# mapleCUx_large_102.net
KiCad netlist of a schematic drawn in EAGLE
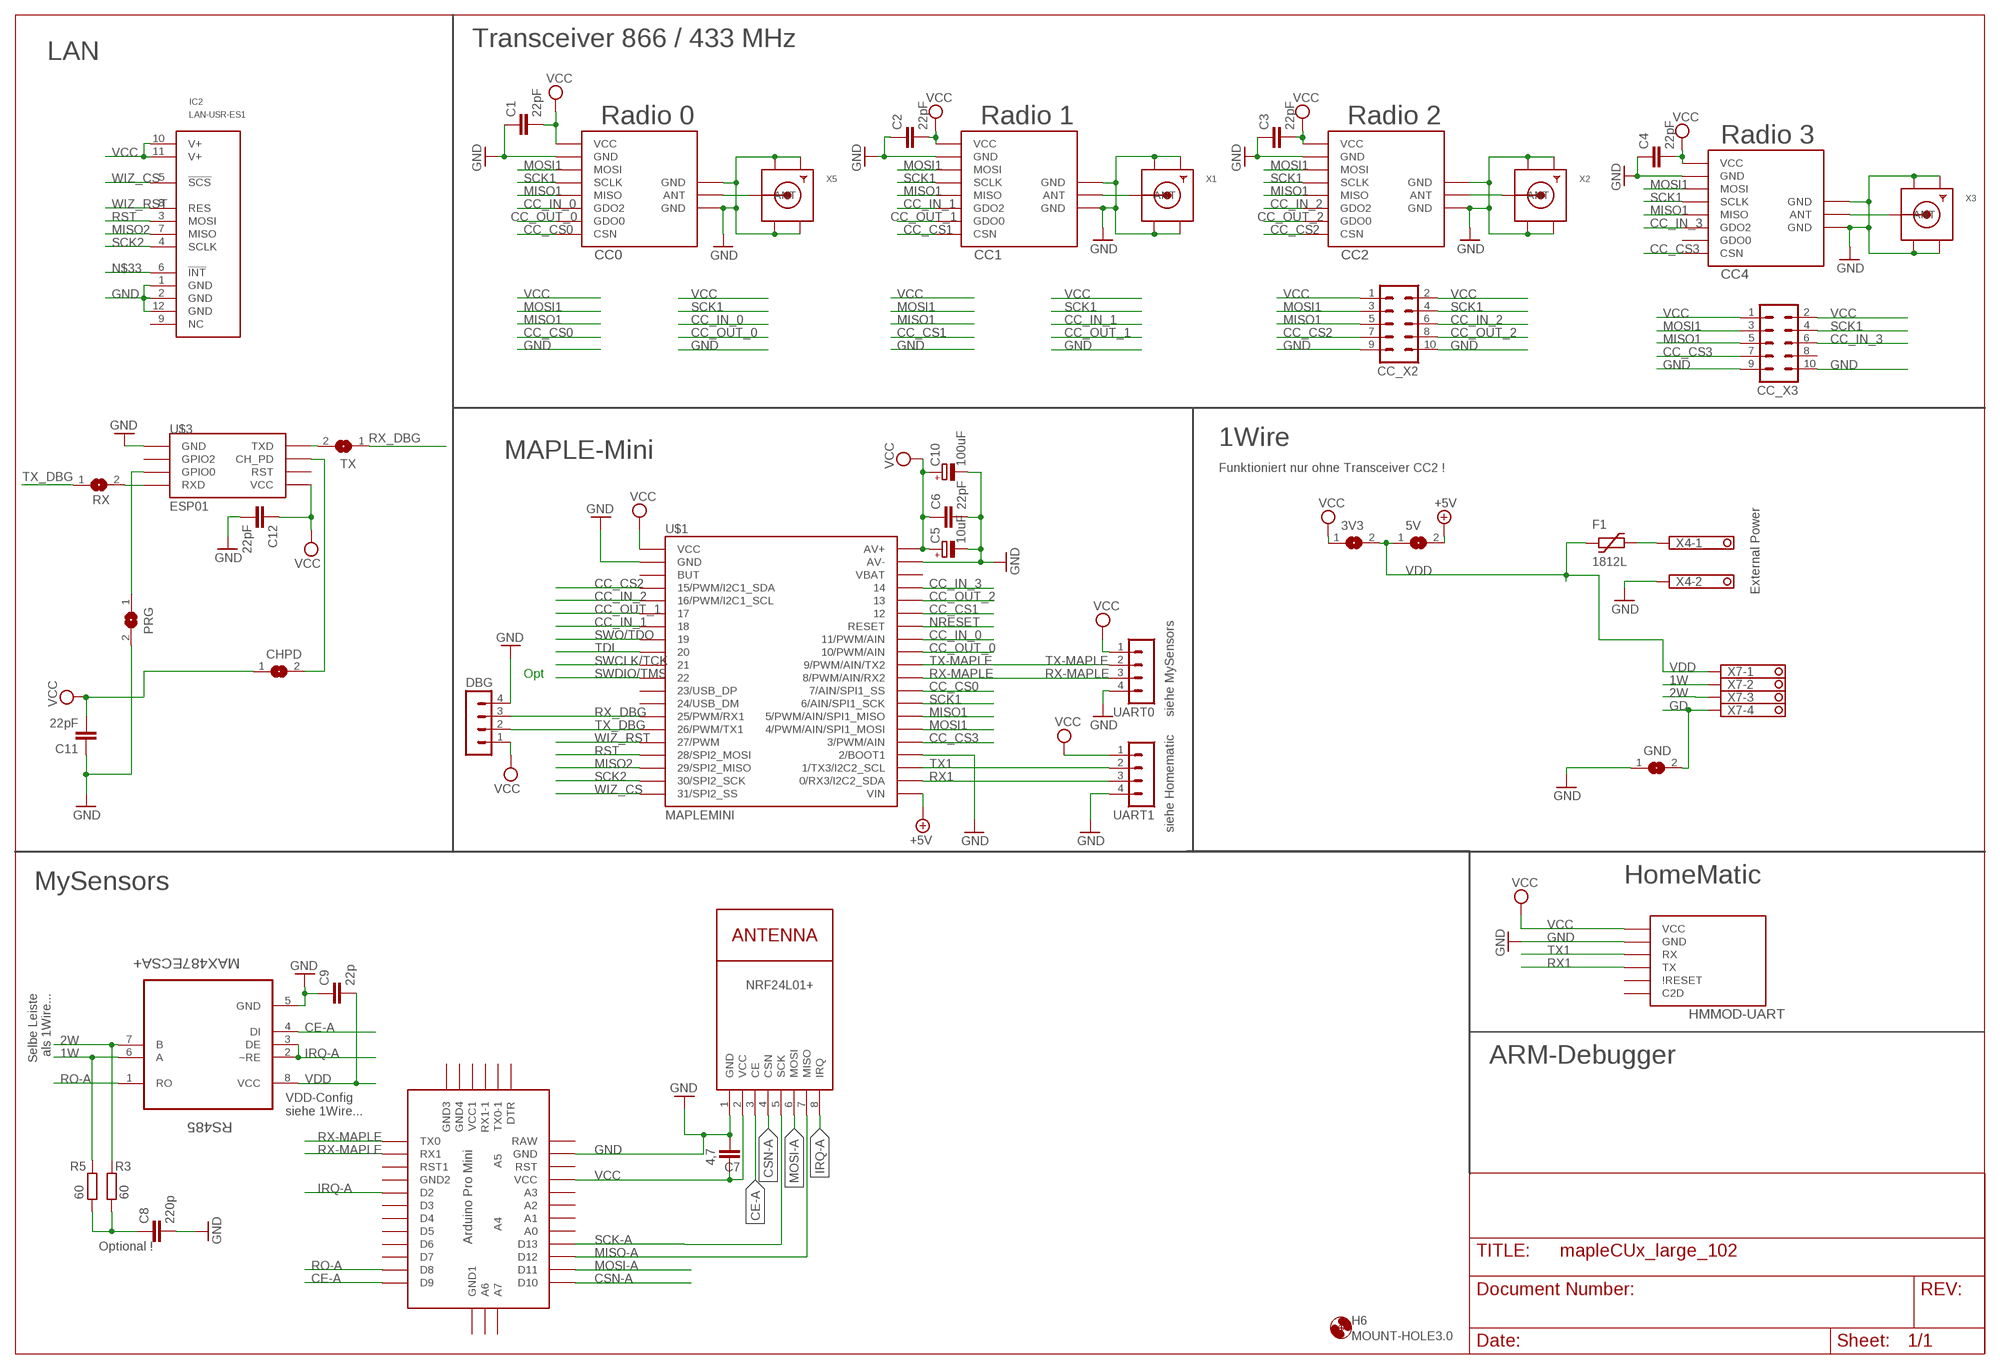
[diagram p0: schematic, sheet 1]

(export (version "E")
  (design (tool "Eeschema 10.0.6"))
  (components
    (comp (ref "3V3") (value "SJ") (footprint "eagle-import:SJ") (libsource (lib "eagle-import") (part "SJ")))
    (comp (ref "5V") (value "SJ") (footprint "eagle-import:SJ") (libsource (lib "eagle-import") (part "SJ")))
    (comp (ref "C1")
      (value "22pF")
      (footprint "eagle-import:C0805")
      (libsource (lib "eagle-import") (part "C-EUC0805"))
    )
    (comp (ref "C2")
      (value "22pF")
      (footprint "eagle-import:C0805")
      (libsource (lib "eagle-import") (part "C-EUC0805"))
    )
    (comp (ref "C3")
      (value "22pF")
      (footprint "eagle-import:C0805")
      (libsource (lib "eagle-import") (part "C-EUC0805"))
    )
    (comp (ref "C4")
      (value "22pF")
      (footprint "eagle-import:C0805")
      (libsource (lib "eagle-import") (part "C-EUC0805"))
    )
    (comp (ref "C5")
      (value "10uF")
      (footprint "eagle-import:R_2012-12W")
      (libsource (lib "eagle-import") (part "CPOL-EUR/2012-12W"))
    )
    (comp (ref "C6")
      (value "22pF")
      (footprint "eagle-import:C0805")
      (libsource (lib "eagle-import") (part "C-EUC0805"))
    )
    (comp (ref "C7")
      (value "4,7")
      (footprint "eagle-import:C1210")
      (libsource (lib "eagle-import") (part "C-EUC1210"))
    )
    (comp (ref "C8")
      (value "220p")
      (footprint "eagle-import:C0805")
      (libsource (lib "eagle-import") (part "C-EUC0805"))
    )
    (comp (ref "C9")
      (value "22p")
      (footprint "eagle-import:C0805")
      (libsource (lib "eagle-import") (part "C-EUC0805"))
    )
    (comp (ref "C10")
      (value "100uF")
      (footprint "eagle-import:E5-8,5")
      (libsource (lib "eagle-import") (part "CPOL-EUE5-8.5"))
    )
    (comp (ref "C11")
      (value "22pF")
      (footprint "eagle-import:C0805")
      (libsource (lib "eagle-import") (part "C-EUC0805"))
    )
    (comp (ref "C12")
      (value "22pF")
      (footprint "eagle-import:C0805")
      (libsource (lib "eagle-import") (part "C-EUC0805"))
    )
    (comp (ref "CC0")
      (value "CC1101")
      (footprint "eagle-import:CC1101_MODULE1_SMD")
      (libsource (lib "eagle-import") (part "CC1101_MODULE1SMD"))
    )
    (comp (ref "CC1")
      (value "CC1101_MODULE1SMD")
      (footprint "eagle-import:CC1101_MODULE1_SMD")
      (libsource (lib "eagle-import") (part "CC1101_MODULE1SMD"))
    )
    (comp (ref "CC2")
      (value "CC1101_MODULE1SMD")
      (footprint "eagle-import:CC1101_MODULE1_SMD")
      (libsource (lib "eagle-import") (part "CC1101_MODULE1SMD"))
    )
    (comp (ref "CC4")
      (value "CC1101_MODULE1SMD")
      (footprint "eagle-import:CC1101_MODULE1_SMD")
      (libsource (lib "eagle-import") (part "CC1101_MODULE1SMD"))
    )
    (comp (ref "CC_X2")
      (value "MA05-2")
      (footprint "eagle-import:MA05-2")
      (libsource (lib "eagle-import") (part "MA05-2"))
    )
    (comp (ref "CC_X3")
      (value "MA05-2")
      (footprint "eagle-import:MA05-2")
      (libsource (lib "eagle-import") (part "MA05-2"))
    )
    (comp (ref "CHPD")
      (value "SJ")
      (footprint "eagle-import:SJ")
      (libsource (lib "eagle-import") (part "SJ"))
    )
    (comp (ref "DBG")
      (value "MA04-1")
      (footprint "eagle-import:MA04-1")
      (libsource (lib "eagle-import") (part "MA04-1"))
    )
    (comp (ref "F1")
      (value "1812L")
      (footprint "eagle-import:1812L")
      (libsource (lib "eagle-import") (part "1812L"))
    )
    (comp (ref "GND") (value "SJ") (footprint "eagle-import:SJ") (libsource (lib "eagle-import") (part "SJ")))
    (comp (ref "H6")
      (value "MOUNT-HOLE3.0")
      (footprint "eagle-import:3,0")
      (libsource (lib "eagle-import") (part "MOUNT-HOLE3.0"))
    )
    (comp (ref "HMMOD-UART")
      (value "HM-MOD-UARTDIL")
      (footprint "eagle-import:HM-MOD-UART-DIL")
      (libsource (lib "eagle-import") (part "HM-MOD-UARTDIL"))
    )
    (comp (ref "IC2")
      (value "LAN-USR-ES1")
      (footprint "eagle-import:USR-ES1")
      (libsource (lib "eagle-import") (part "LAN-USR-ES1"))
    )
    (comp (ref "NRF24L01+")
      (value "NRF24L01+")
      (footprint "eagle-import:WIRELESS-NRF24L01")
      (libsource (lib "eagle-import") (part "WIRELESS-NRF24L01"))
    )
    (comp (ref "PRG") (value "SJ") (footprint "eagle-import:SJ") (libsource (lib "eagle-import") (part "SJ")))
    (comp (ref "R3")
      (value "60")
      (footprint "eagle-import:R0805")
      (libsource (lib "eagle-import") (part "R-EU_R0805"))
    )
    (comp (ref "R5")
      (value "60")
      (footprint "eagle-import:R0805")
      (libsource (lib "eagle-import") (part "R-EU_R0805"))
    )
    (comp (ref "RS485")
      (value "MAX487ECSA+")
      (footprint "eagle-import:SOIC127P600X175-8N")
      (libsource (lib "eagle-import") (part "MAX487ECSA+"))
    )
    (comp (ref "RX") (value "SJ") (footprint "eagle-import:SJ") (libsource (lib "eagle-import") (part "SJ")))
    (comp (ref "TX") (value "SJ") (footprint "eagle-import:SJ") (libsource (lib "eagle-import") (part "SJ")))
    (comp (ref "U$1")
      (value "MAPLEMINI")
      (footprint "eagle-import:20-DIP")
      (libsource (lib "eagle-import") (part "MAPLEMINI"))
    )
    (comp (ref "U$2")
      (value "ABK-PRO-MINI")
      (footprint "eagle-import:ABK-PRO-MINI")
      (libsource (lib "eagle-import") (part "ABK-PRO-MINI"))
    )
    (comp (ref "U$3")
      (value "ESP01")
      (footprint "eagle-import:ESP01")
      (libsource (lib "eagle-import") (part "ESP01"))
    )
    (comp (ref "UART0")
      (value "MA04-1")
      (footprint "eagle-import:MA04-1")
      (libsource (lib "eagle-import") (part "MA04-1"))
    )
    (comp (ref "UART1")
      (value "MA04-1")
      (footprint "eagle-import:MA04-1")
      (libsource (lib "eagle-import") (part "MA04-1"))
    )
    (comp (ref "X1")
      (value "SMACONNECTOR_EDGE_UFL")
      (footprint "eagle-import:SMA_EDGELAUNCH_UFL")
      (libsource (lib "eagle-import") (part "SMACONNECTOR_EDGE_UFL"))
    )
    (comp (ref "X2")
      (value "SMACONNECTOR_EDGE_UFL")
      (footprint "eagle-import:SMA_EDGELAUNCH_UFL")
      (libsource (lib "eagle-import") (part "SMACONNECTOR_EDGE_UFL"))
    )
    (comp (ref "X3")
      (value "SMACONNECTOR_EDGE_UFL")
      (footprint "eagle-import:SMA_EDGELAUNCH_UFL")
      (libsource (lib "eagle-import") (part "SMACONNECTOR_EDGE_UFL"))
    )
    (comp (ref "X4")
      (value "1751248")
      (footprint "eagle-import:1751248")
      (libsource (lib "eagle-import") (part "1751248"))
    )
    (comp (ref "X5")
      (value "SMACONNECTOR_EDGE_UFL")
      (footprint "eagle-import:SMA_EDGELAUNCH_UFL")
      (libsource (lib "eagle-import") (part "SMACONNECTOR_EDGE_UFL"))
    )
    (comp (ref "X7")
      (value "1751264")
      (footprint "eagle-import:1751264")
      (libsource (lib "eagle-import") (part "1751264"))
    )
  )
  (nets
    (net (code "1") (name "+5V") (class "Default")
      (node (ref "5V") (pin "2") (pinfunction "2_2") (pintype "passive"))
      (node (ref "U$1") (pin "21") (pinfunction "VIN_21") (pintype "bidirectional"))
    )
    (net (code "2") (name "/1W") (class "Default")
      (node (ref "R5") (pin "2") (pinfunction "2_2") (pintype "passive"))
      (node (ref "RS485") (pin "6") (pinfunction "A_6") (pintype "bidirectional"))
      (node (ref "X7") (pin "2") (pinfunction "K_2") (pintype "passive"))
    )
    (net (code "3") (name "/2W") (class "Default")
      (node (ref "R3") (pin "2") (pinfunction "2_2") (pintype "passive"))
      (node (ref "RS485") (pin "7") (pinfunction "B_7") (pintype "bidirectional"))
      (node (ref "X7") (pin "3") (pinfunction "K_3") (pintype "passive"))
    )
    (net (code "4") (name "/CC_CS0") (class "Default")
      (node (ref "CC0") (pin "CSN") (pinfunction "CSN_CSN") (pintype "bidirectional"))
      (node (ref "U$1") (pin "29") (pinfunction "7/AIN/SPI1_SS_29") (pintype "bidirectional"))
    )
    (net (code "5") (name "/CC_CS1") (class "Default")
      (node (ref "CC1") (pin "CSN") (pinfunction "CSN_CSN") (pintype "bidirectional"))
      (node (ref "U$1") (pin "35") (pinfunction "12_35") (pintype "bidirectional"))
    )
    (net (code "6") (name "/CC_CS2") (class "Default")
      (node (ref "CC2") (pin "CSN") (pinfunction "CSN_CSN") (pintype "bidirectional"))
      (node (ref "CC_X2") (pin "7") (pinfunction "7_7") (pintype "passive"))
      (node (ref "U$1") (pin "4") (pinfunction "15/PWM/I2C1_SDA_4") (pintype "bidirectional"))
    )
    (net (code "7") (name "/CC_CS3") (class "Default")
      (node (ref "CC4") (pin "CSN") (pinfunction "CSN_CSN") (pintype "bidirectional"))
      (node (ref "CC_X3") (pin "7") (pinfunction "7_7") (pintype "passive"))
      (node (ref "U$1") (pin "25") (pinfunction "3/PWM/AIN_25") (pintype "bidirectional"))
    )
    (net (code "8") (name "/CC_IN_0") (class "Default")
      (node (ref "CC0") (pin "GDO2") (pinfunction "GDO2_GDO2") (pintype "bidirectional"))
      (node (ref "U$1") (pin "33") (pinfunction "11/PWM/AIN_33") (pintype "bidirectional"))
    )
    (net (code "9") (name "/CC_IN_1") (class "Default")
      (node (ref "CC1") (pin "GDO2") (pinfunction "GDO2_GDO2") (pintype "bidirectional"))
      (node (ref "U$1") (pin "7") (pinfunction "18_7") (pintype "bidirectional"))
    )
    (net (code "10") (name "/CC_IN_2") (class "Default")
      (node (ref "CC2") (pin "GDO2") (pinfunction "GDO2_GDO2") (pintype "bidirectional"))
      (node (ref "CC_X2") (pin "6") (pinfunction "6_6") (pintype "passive"))
      (node (ref "U$1") (pin "5") (pinfunction "16/PWM/I2C1_SCL_5") (pintype "bidirectional"))
    )
    (net (code "11") (name "/CC_IN_3") (class "Default")
      (node (ref "CC4") (pin "GDO2") (pinfunction "GDO2_GDO2") (pintype "bidirectional"))
      (node (ref "CC_X3") (pin "6") (pinfunction "6_6") (pintype "passive"))
      (node (ref "U$1") (pin "37") (pinfunction "14_37") (pintype "bidirectional"))
    )
    (net (code "12") (name "/CC_OUT_0") (class "Default")
      (node (ref "CC0") (pin "GDO0") (pinfunction "GDO0_GDO0") (pintype "bidirectional"))
      (node (ref "U$1") (pin "32") (pinfunction "10/PWM/AIN_32") (pintype "bidirectional"))
    )
    (net (code "13") (name "/CC_OUT_1") (class "Default")
      (node (ref "CC1") (pin "GDO0") (pinfunction "GDO0_GDO0") (pintype "bidirectional"))
      (node (ref "U$1") (pin "6") (pinfunction "17_6") (pintype "bidirectional"))
    )
    (net (code "14") (name "/CC_OUT_2") (class "Default")
      (node (ref "CC2") (pin "GDO0") (pinfunction "GDO0_GDO0") (pintype "bidirectional"))
      (node (ref "CC_X2") (pin "8") (pinfunction "8_8") (pintype "passive"))
      (node (ref "U$1") (pin "36") (pinfunction "13_36") (pintype "bidirectional"))
    )
    (net (code "15") (name "/GD") (class "Default")
      (node (ref "GND") (pin "2") (pinfunction "2_2") (pintype "passive"))
      (node (ref "X7") (pin "4") (pinfunction "K_4") (pintype "passive"))
    )
    (net (code "16") (name "/MISO-A") (class "Default")
      (node (ref "NRF24L01+") (pin "7") (pinfunction "MISO_7") (pintype "bidirectional"))
      (node (ref "U$2") (pin "D12") (pinfunction "D12_D12") (pintype "bidirectional"))
    )
    (net (code "17") (name "/MISO1") (class "Default")
      (node (ref "CC0") (pin "MISO") (pinfunction "MISO_MISO") (pintype "bidirectional"))
      (node (ref "CC1") (pin "MISO") (pinfunction "MISO_MISO") (pintype "bidirectional"))
      (node (ref "CC2") (pin "MISO") (pinfunction "MISO_MISO") (pintype "bidirectional"))
      (node (ref "CC4") (pin "MISO") (pinfunction "MISO_MISO") (pintype "bidirectional"))
      (node (ref "CC_X2") (pin "5") (pinfunction "5_5") (pintype "passive"))
      (node (ref "CC_X3") (pin "5") (pinfunction "5_5") (pintype "passive"))
      (node (ref "U$1") (pin "27") (pinfunction "5/PWM/AIN/SPI1_MISO_27") (pintype "bidirectional"))
    )
    (net (code "18") (name "/MISO2") (class "Default")
      (node (ref "IC2") (pin "7") (pinfunction "MISO_7") (pintype "bidirectional"))
      (node (ref "U$1") (pin "18") (pinfunction "29/SPI2_MISO_18") (pintype "bidirectional"))
    )
    (net (code "19") (name "/MOSI1") (class "Default")
      (node (ref "CC0") (pin "MOSI") (pinfunction "MOSI_MOSI") (pintype "bidirectional"))
      (node (ref "CC1") (pin "MOSI") (pinfunction "MOSI_MOSI") (pintype "bidirectional"))
      (node (ref "CC2") (pin "MOSI") (pinfunction "MOSI_MOSI") (pintype "bidirectional"))
      (node (ref "CC4") (pin "MOSI") (pinfunction "MOSI_MOSI") (pintype "bidirectional"))
      (node (ref "CC_X2") (pin "3") (pinfunction "3_3") (pintype "passive"))
      (node (ref "CC_X3") (pin "3") (pinfunction "3_3") (pintype "passive"))
      (node (ref "U$1") (pin "26") (pinfunction "4/PWM/AIN/SPI1_MOSI_26") (pintype "bidirectional"))
    )
    (net (code "20") (name "/N$33") (class "Default")
      (node (ref "IC2") (pin "6") (pinfunction "~{INT}_6") (pintype "output"))
    )
    (net (code "21") (name "/NRESET") (class "Default")
      (node (ref "U$1") (pin "34") (pinfunction "RESET_34") (pintype "bidirectional"))
    )
    (net (code "22") (name "/RO-A") (class "Default")
      (node (ref "RS485") (pin "1") (pinfunction "RO_1") (pintype "output"))
      (node (ref "U$2") (pin "D8") (pinfunction "D8_D8") (pintype "bidirectional"))
    )
    (net (code "23") (name "/RST") (class "Default")
      (node (ref "IC2") (pin "3") (pinfunction "MOSI_3") (pintype "bidirectional"))
      (node (ref "U$1") (pin "17") (pinfunction "28/SPI2_MOSI_17") (pintype "bidirectional"))
    )
    (net (code "24") (name "/RX-MAPLE") (class "Default")
      (node (ref "U$1") (pin "30") (pinfunction "8/PWM/AIN/RX2_30") (pintype "bidirectional"))
      (node (ref "U$2") (pin "RX1") (pinfunction "RX1_RX1") (pintype "bidirectional"))
      (node (ref "U$2") (pin "TX0") (pinfunction "TX0_TX0") (pintype "bidirectional"))
      (node (ref "UART0") (pin "3") (pinfunction "3_3") (pintype "passive"))
    )
    (net (code "25") (name "/RX1") (class "Default")
      (node (ref "HMMOD-UART") (pin "5") (pinfunction "TX_5") (pintype "bidirectional"))
      (node (ref "U$1") (pin "22") (pinfunction "0/RX3/I2C2_SDA_22") (pintype "bidirectional"))
      (node (ref "UART1") (pin "3") (pinfunction "3_3") (pintype "passive"))
    )
    (net (code "26") (name "/RX_DBG") (class "Default")
      (node (ref "DBG") (pin "3") (pinfunction "3_3") (pintype "passive"))
      (node (ref "TX") (pin "1") (pinfunction "1_1") (pintype "passive"))
      (node (ref "U$1") (pin "14") (pinfunction "25/PWM/RX1_14") (pintype "bidirectional"))
    )
    (net (code "27") (name "/SCK-A") (class "Default")
      (node (ref "NRF24L01+") (pin "5") (pinfunction "SCK_5") (pintype "bidirectional"))
      (node (ref "U$2") (pin "D13") (pinfunction "D13_D13") (pintype "bidirectional"))
    )
    (net (code "28") (name "/SCK1") (class "Default")
      (node (ref "CC0") (pin "SCLK") (pinfunction "SCLK_SCLK") (pintype "bidirectional"))
      (node (ref "CC1") (pin "SCLK") (pinfunction "SCLK_SCLK") (pintype "bidirectional"))
      (node (ref "CC2") (pin "SCLK") (pinfunction "SCLK_SCLK") (pintype "bidirectional"))
      (node (ref "CC4") (pin "SCLK") (pinfunction "SCLK_SCLK") (pintype "bidirectional"))
      (node (ref "CC_X2") (pin "4") (pinfunction "4_4") (pintype "passive"))
      (node (ref "CC_X3") (pin "4") (pinfunction "4_4") (pintype "passive"))
      (node (ref "U$1") (pin "28") (pinfunction "6/AIN/SPI1_SCK_28") (pintype "bidirectional"))
    )
    (net (code "29") (name "/SCK2") (class "Default")
      (node (ref "IC2") (pin "4") (pinfunction "SCLK_4") (pintype "input"))
      (node (ref "U$1") (pin "19") (pinfunction "30/SPI2_SCK_19") (pintype "bidirectional"))
    )
    (net (code "30") (name "/SWCLK{slash}TCK") (class "Default")
      (node (ref "U$1") (pin "10") (pinfunction "21_10") (pintype "bidirectional"))
    )
    (net (code "31") (name "/SWDIO{slash}TMS") (class "Default")
      (node (ref "U$1") (pin "11") (pinfunction "22_11") (pintype "bidirectional"))
    )
    (net (code "32") (name "/SWO{slash}TDO") (class "Default")
      (node (ref "U$1") (pin "8") (pinfunction "19_8") (pintype "bidirectional"))
    )
    (net (code "33") (name "/TDI") (class "Default")
      (node (ref "U$1") (pin "9") (pinfunction "20_9") (pintype "bidirectional"))
    )
    (net (code "34") (name "/TX-MAPLE") (class "Default")
      (node (ref "U$1") (pin "31") (pinfunction "9/PWM/AIN/TX2_31") (pintype "bidirectional"))
      (node (ref "UART0") (pin "2") (pinfunction "2_2") (pintype "passive"))
    )
    (net (code "35") (name "/TX1") (class "Default")
      (node (ref "HMMOD-UART") (pin "6") (pinfunction "RX_6") (pintype "bidirectional"))
      (node (ref "U$1") (pin "23") (pinfunction "1/TX3/I2C2_SCL_23") (pintype "bidirectional"))
      (node (ref "UART1") (pin "2") (pinfunction "2_2") (pintype "passive"))
    )
    (net (code "36") (name "/TX_DBG") (class "Default")
      (node (ref "DBG") (pin "2") (pinfunction "2_2") (pintype "passive"))
      (node (ref "RX") (pin "1") (pinfunction "1_1") (pintype "passive"))
      (node (ref "U$1") (pin "15") (pinfunction "26/PWM/TX1_15") (pintype "bidirectional"))
    )
    (net (code "37") (name "/VDD") (class "Default")
      (node (ref "3V3") (pin "2") (pinfunction "2_2") (pintype "passive"))
      (node (ref "5V") (pin "1") (pinfunction "1_1") (pintype "passive"))
      (node (ref "C9") (pin "2") (pinfunction "2_2") (pintype "passive"))
      (node (ref "F1") (pin "P$1") (pinfunction "1_P$1") (pintype "passive"))
      (node (ref "RS485") (pin "8") (pinfunction "VCC_8") (pintype "power_in"))
      (node (ref "X7") (pin "1") (pinfunction "K_1") (pintype "passive"))
    )
    (net (code "38") (name "/WIZ_CS") (class "Default")
      (node (ref "IC2") (pin "5") (pinfunction "~{SCS}_5") (pintype "input"))
      (node (ref "U$1") (pin "20") (pinfunction "31/SPI2_SS_20") (pintype "bidirectional"))
    )
    (net (code "39") (name "/WIZ_RST") (class "Default")
      (node (ref "IC2") (pin "8") (pinfunction "RES_8") (pintype "input"))
      (node (ref "U$1") (pin "16") (pinfunction "27/PWM_16") (pintype "bidirectional"))
    )
    (net (code "40") (name "CE-A") (class "Default")
      (node (ref "NRF24L01+") (pin "3") (pinfunction "CE_3") (pintype "bidirectional"))
      (node (ref "RS485") (pin "4") (pinfunction "DI_4") (pintype "input"))
      (node (ref "U$2") (pin "D9") (pinfunction "D9_D9") (pintype "bidirectional"))
    )
    (net (code "41") (name "CSN-A") (class "Default")
      (node (ref "NRF24L01+") (pin "4") (pinfunction "CSN_4") (pintype "bidirectional"))
      (node (ref "U$2") (pin "D10") (pinfunction "D10_D10") (pintype "bidirectional"))
    )
    (net (code "42") (name "GND") (class "Default")
      (node (ref "C1") (pin "1") (pinfunction "1_1") (pintype "passive"))
      (node (ref "C10") (pin "-") (pinfunction "-_-") (pintype "passive"))
      (node (ref "C11") (pin "1") (pinfunction "1_1") (pintype "passive"))
      (node (ref "C12") (pin "2") (pinfunction "2_2") (pintype "passive"))
      (node (ref "C2") (pin "1") (pinfunction "1_1") (pintype "passive"))
      (node (ref "C3") (pin "1") (pinfunction "1_1") (pintype "passive"))
      (node (ref "C4") (pin "1") (pinfunction "1_1") (pintype "passive"))
      (node (ref "C5") (pin "-") (pinfunction "-_-") (pintype "passive"))
      (node (ref "C6") (pin "2") (pinfunction "2_2") (pintype "passive"))
      (node (ref "C7") (pin "1") (pinfunction "1_1") (pintype "passive"))
      (node (ref "C8") (pin "2") (pinfunction "2_2") (pintype "passive"))
      (node (ref "C9") (pin "1") (pinfunction "1_1") (pintype "passive"))
      (node (ref "CC0") (pin "GND@0") (pinfunction "GND_GND@0") (pintype "power_in"))
      (node (ref "CC0") (pin "GND@1") (pinfunction "GND_GND@1") (pintype "power_in"))
      (node (ref "CC0") (pin "GND@2") (pinfunction "GND_GND@2") (pintype "power_in"))
      (node (ref "CC1") (pin "GND@0") (pinfunction "GND_GND@0") (pintype "power_in"))
      (node (ref "CC1") (pin "GND@1") (pinfunction "GND_GND@1") (pintype "power_in"))
      (node (ref "CC1") (pin "GND@2") (pinfunction "GND_GND@2") (pintype "power_in"))
      (node (ref "CC2") (pin "GND@0") (pinfunction "GND_GND@0") (pintype "power_in"))
      (node (ref "CC2") (pin "GND@1") (pinfunction "GND_GND@1") (pintype "power_in"))
      (node (ref "CC2") (pin "GND@2") (pinfunction "GND_GND@2") (pintype "power_in"))
      (node (ref "CC4") (pin "GND@0") (pinfunction "GND_GND@0") (pintype "power_in"))
      (node (ref "CC4") (pin "GND@1") (pinfunction "GND_GND@1") (pintype "power_in"))
      (node (ref "CC4") (pin "GND@2") (pinfunction "GND_GND@2") (pintype "power_in"))
      (node (ref "CC_X2") (pin "10") (pinfunction "10_10") (pintype "passive"))
      (node (ref "CC_X2") (pin "9") (pinfunction "9_9") (pintype "passive"))
      (node (ref "CC_X3") (pin "10") (pinfunction "10_10") (pintype "passive"))
      (node (ref "CC_X3") (pin "9") (pinfunction "9_9") (pintype "passive"))
      (node (ref "DBG") (pin "4") (pinfunction "4_4") (pintype "passive"))
      (node (ref "GND") (pin "1") (pinfunction "1_1") (pintype "passive"))
      (node (ref "HMMOD-UART") (pin "2") (pinfunction "GND_2") (pintype "power_in"))
      (node (ref "IC2") (pin "1") (pinfunction "GND_1") (pintype "power_in"))
      (node (ref "IC2") (pin "12") (pinfunction "GND_12") (pintype "power_in"))
      (node (ref "IC2") (pin "2") (pinfunction "GND_2") (pintype "power_in"))
      (node (ref "NRF24L01+") (pin "1") (pinfunction "GND_1") (pintype "power_in"))
      (node (ref "PRG") (pin "2") (pinfunction "2_2") (pintype "passive"))
      (node (ref "RS485") (pin "5") (pinfunction "GND_5") (pintype "passive"))
      (node (ref "U$1") (pin "2") (pinfunction "GND_2") (pintype "bidirectional"))
      (node (ref "U$1") (pin "24") (pinfunction "2/BOOT1_24") (pintype "bidirectional"))
      (node (ref "U$1") (pin "39") (pinfunction "AV-_39") (pintype "bidirectional"))
      (node (ref "U$2") (pin "GND") (pinfunction "GND_GND") (pintype "bidirectional"))
      (node (ref "U$3") (pin "GND") (pinfunction "GND_GND") (pintype "bidirectional"))
      (node (ref "UART0") (pin "4") (pinfunction "4_4") (pintype "passive"))
      (node (ref "UART1") (pin "4") (pinfunction "4_4") (pintype "passive"))
      (node (ref "X1") (pin "GND@1") (pinfunction "GND1_GND@1") (pintype "power_in"))
      (node (ref "X1") (pin "GND@2") (pinfunction "GND2_GND@2") (pintype "power_in"))
      (node (ref "X1") (pin "GND@3") (pinfunction "GND3_GND@3") (pintype "power_in"))
      (node (ref "X1") (pin "GND@4") (pinfunction "GND4_GND@4") (pintype "power_in"))
      (node (ref "X2") (pin "GND@1") (pinfunction "GND1_GND@1") (pintype "power_in"))
      (node (ref "X2") (pin "GND@2") (pinfunction "GND2_GND@2") (pintype "power_in"))
      (node (ref "X2") (pin "GND@3") (pinfunction "GND3_GND@3") (pintype "power_in"))
      (node (ref "X2") (pin "GND@4") (pinfunction "GND4_GND@4") (pintype "power_in"))
      (node (ref "X3") (pin "GND@1") (pinfunction "GND1_GND@1") (pintype "power_in"))
      (node (ref "X3") (pin "GND@2") (pinfunction "GND2_GND@2") (pintype "power_in"))
      (node (ref "X3") (pin "GND@3") (pinfunction "GND3_GND@3") (pintype "power_in"))
      (node (ref "X3") (pin "GND@4") (pinfunction "GND4_GND@4") (pintype "power_in"))
      (node (ref "X4") (pin "2") (pinfunction "K_2") (pintype "passive"))
      (node (ref "X5") (pin "GND@1") (pinfunction "GND1_GND@1") (pintype "power_in"))
      (node (ref "X5") (pin "GND@2") (pinfunction "GND2_GND@2") (pintype "power_in"))
      (node (ref "X5") (pin "GND@3") (pinfunction "GND3_GND@3") (pintype "power_in"))
      (node (ref "X5") (pin "GND@4") (pinfunction "GND4_GND@4") (pintype "power_in"))
    )
    (net (code "43") (name "IRQ-A") (class "Default")
      (node (ref "NRF24L01+") (pin "8") (pinfunction "IRQ_8") (pintype "bidirectional"))
      (node (ref "RS485") (pin "2") (pinfunction "~{RE}_2") (pintype "input"))
      (node (ref "RS485") (pin "3") (pinfunction "DE_3") (pintype "input"))
      (node (ref "U$2") (pin "D2") (pinfunction "D2_D2") (pintype "bidirectional"))
    )
    (net (code "44") (name "MOSI-A") (class "Default")
      (node (ref "NRF24L01+") (pin "6") (pinfunction "MOSI_6") (pintype "bidirectional"))
      (node (ref "U$2") (pin "D11") (pinfunction "D11_D11") (pintype "bidirectional"))
    )
    (net (code "45") (name "Net-(C8-Pad1)") (class "Default")
      (node (ref "C8") (pin "1") (pinfunction "1_1") (pintype "passive"))
      (node (ref "R3") (pin "1") (pinfunction "1_1") (pintype "passive"))
      (node (ref "R5") (pin "1") (pinfunction "1_1") (pintype "passive"))
    )
    (net (code "46") (name "Net-(CHPD-Pad2)") (class "Default")
      (node (ref "CHPD") (pin "2") (pinfunction "2_2") (pintype "passive"))
      (node (ref "U$3") (pin "CH_PD") (pinfunction "CH_PD_CH_PD") (pintype "bidirectional"))
    )
    (net (code "47") (name "Net-(F1-2)") (class "Default")
      (node (ref "F1") (pin "P$2") (pinfunction "2_P$2") (pintype "passive"))
      (node (ref "X4") (pin "1") (pinfunction "K_1") (pintype "passive"))
    )
    (net (code "48") (name "Net-(PRG-Pad1)") (class "Default")
      (node (ref "PRG") (pin "1") (pinfunction "1_1") (pintype "passive"))
      (node (ref "U$3") (pin "GPIO0") (pinfunction "GPIO0_GPIO0") (pintype "bidirectional"))
    )
    (net (code "49") (name "Net-(U$3-RXD)") (class "Default")
      (node (ref "RX") (pin "2") (pinfunction "2_2") (pintype "passive"))
      (node (ref "U$3") (pin "RX") (pinfunction "RXD_RX") (pintype "bidirectional"))
    )
    (net (code "50") (name "Net-(U$3-TXD)") (class "Default")
      (node (ref "TX") (pin "2") (pinfunction "2_2") (pintype "passive"))
      (node (ref "U$3") (pin "TX") (pinfunction "TXD_TX") (pintype "bidirectional"))
    )
    (net (code "51") (name "Net-(X1-ANT)") (class "Default")
      (node (ref "CC1") (pin "ANT") (pinfunction "ANT_ANT") (pintype "output"))
      (node (ref "X1") (pin "P") (pinfunction "ANT_P") (pintype "bidirectional"))
    )
    (net (code "52") (name "Net-(X2-ANT)") (class "Default")
      (node (ref "CC2") (pin "ANT") (pinfunction "ANT_ANT") (pintype "output"))
      (node (ref "X2") (pin "P") (pinfunction "ANT_P") (pintype "bidirectional"))
    )
    (net (code "53") (name "Net-(X3-ANT)") (class "Default")
      (node (ref "CC4") (pin "ANT") (pinfunction "ANT_ANT") (pintype "output"))
      (node (ref "X3") (pin "P") (pinfunction "ANT_P") (pintype "bidirectional"))
    )
    (net (code "54") (name "Net-(X5-ANT)") (class "Default")
      (node (ref "CC0") (pin "ANT") (pinfunction "ANT_ANT") (pintype "output"))
      (node (ref "X5") (pin "P") (pinfunction "ANT_P") (pintype "bidirectional"))
    )
    (net (code "55") (name "VCC") (class "Default")
      (node (ref "3V3") (pin "1") (pinfunction "1_1") (pintype "passive"))
      (node (ref "C1") (pin "2") (pinfunction "2_2") (pintype "passive"))
      (node (ref "C10") (pin "+") (pinfunction "+_+") (pintype "passive"))
      (node (ref "C11") (pin "2") (pinfunction "2_2") (pintype "passive"))
      (node (ref "C12") (pin "1") (pinfunction "1_1") (pintype "passive"))
      (node (ref "C2") (pin "2") (pinfunction "2_2") (pintype "passive"))
      (node (ref "C3") (pin "2") (pinfunction "2_2") (pintype "passive"))
      (node (ref "C4") (pin "2") (pinfunction "2_2") (pintype "passive"))
      (node (ref "C5") (pin "+") (pinfunction "+_+") (pintype "passive"))
      (node (ref "C6") (pin "1") (pinfunction "1_1") (pintype "passive"))
      (node (ref "C7") (pin "2") (pinfunction "2_2") (pintype "passive"))
      (node (ref "CC0") (pin "VCC") (pinfunction "VCC_VCC") (pintype "power_in"))
      (node (ref "CC1") (pin "VCC") (pinfunction "VCC_VCC") (pintype "power_in"))
      (node (ref "CC2") (pin "VCC") (pinfunction "VCC_VCC") (pintype "power_in"))
      (node (ref "CC4") (pin "VCC") (pinfunction "VCC_VCC") (pintype "power_in"))
      (node (ref "CC_X2") (pin "1") (pinfunction "1_1") (pintype "passive"))
      (node (ref "CC_X2") (pin "2") (pinfunction "2_2") (pintype "passive"))
      (node (ref "CC_X3") (pin "1") (pinfunction "1_1") (pintype "passive"))
      (node (ref "CC_X3") (pin "2") (pinfunction "2_2") (pintype "passive"))
      (node (ref "CHPD") (pin "1") (pinfunction "1_1") (pintype "passive"))
      (node (ref "DBG") (pin "1") (pinfunction "1_1") (pintype "passive"))
      (node (ref "HMMOD-UART") (pin "1") (pinfunction "VCC_1") (pintype "power_in"))
      (node (ref "IC2") (pin "10") (pinfunction "V+_10") (pintype "power_in"))
      (node (ref "IC2") (pin "11") (pinfunction "V+_11") (pintype "power_in"))
      (node (ref "NRF24L01+") (pin "2") (pinfunction "VCC_2") (pintype "power_in"))
      (node (ref "U$1") (pin "1") (pinfunction "VCC_1") (pintype "bidirectional"))
      (node (ref "U$1") (pin "40") (pinfunction "AV+_40") (pintype "bidirectional"))
      (node (ref "U$2") (pin "VCC") (pinfunction "VCC_VCC") (pintype "bidirectional"))
      (node (ref "U$3") (pin "VCC") (pinfunction "VCC_VCC") (pintype "bidirectional"))
      (node (ref "UART0") (pin "1") (pinfunction "1_1") (pintype "passive"))
      (node (ref "UART1") (pin "1") (pinfunction "1_1") (pintype "passive"))
    )
    (net (code "56") (name "unconnected-(CC4-PadGDO0)") (class "Default")
      (node (ref "CC4") (pin "GDO0") (pinfunction "GDO0_GDO0") (pintype "bidirectional"))
    )
    (net (code "57") (name "unconnected-(CC_X3-Pad8)") (class "Default")
      (node (ref "CC_X3") (pin "8") (pinfunction "8_8") (pintype "passive"))
    )
    (net (code "58") (name "unconnected-(HMMOD-UART-C2D-Pad3)") (class "Default")
      (node (ref "HMMOD-UART") (pin "3") (pinfunction "C2D_3") (pintype "bidirectional"))
    )
    (net (code "59") (name "unconnected-(HMMOD-UART-\\~{RESET}-Pad4)") (class "Default")
      (node (ref "HMMOD-UART") (pin "4") (pinfunction "\\~{RESET}_4") (pintype "bidirectional"))
    )
    (net (code "60") (name "unconnected-(IC2-NC-Pad9)") (class "Default")
      (node (ref "IC2") (pin "9") (pinfunction "NC_9") (pintype "no_connect"))
    )
    (net (code "61") (name "unconnected-(U$1-23{slash}USB_DP-Pad12)") (class "Default")
      (node (ref "U$1") (pin "12") (pinfunction "23/USB_DP_12") (pintype "bidirectional"))
    )
    (net (code "62") (name "unconnected-(U$1-24{slash}USB_DM-Pad13)") (class "Default")
      (node (ref "U$1") (pin "13") (pinfunction "24/USB_DM_13") (pintype "bidirectional"))
    )
    (net (code "63") (name "unconnected-(U$1-BUT-Pad3)") (class "Default")
      (node (ref "U$1") (pin "3") (pinfunction "BUT_3") (pintype "bidirectional"))
    )
    (net (code "64") (name "unconnected-(U$1-VBAT-Pad38)") (class "Default")
      (node (ref "U$1") (pin "38") (pinfunction "VBAT_38") (pintype "bidirectional"))
    )
    (net (code "65") (name "unconnected-(U$2-GND1-PadGND4)") (class "Default")
      (node (ref "U$2") (pin "GND4") (pinfunction "GND1_GND4") (pintype "bidirectional"))
    )
    (net (code "66") (name "unconnected-(U$2-GND2-PadGND1)") (class "Default")
      (node (ref "U$2") (pin "GND1") (pinfunction "GND2_GND1") (pintype "bidirectional"))
    )
    (net (code "67") (name "unconnected-(U$2-GND3-PadGND2)") (class "Default")
      (node (ref "U$2") (pin "GND2") (pinfunction "GND3_GND2") (pintype "bidirectional"))
    )
    (net (code "68") (name "unconnected-(U$2-GND4-PadGND3)") (class "Default")
      (node (ref "U$2") (pin "GND3") (pinfunction "GND4_GND3") (pintype "bidirectional"))
    )
    (net (code "69") (name "unconnected-(U$2-PadA0)") (class "Default")
      (node (ref "U$2") (pin "A0") (pinfunction "A0_A0") (pintype "bidirectional"))
    )
    (net (code "70") (name "unconnected-(U$2-PadA1)") (class "Default")
      (node (ref "U$2") (pin "A1") (pinfunction "A1_A1") (pintype "bidirectional"))
    )
    (net (code "71") (name "unconnected-(U$2-PadA2)") (class "Default")
      (node (ref "U$2") (pin "A2") (pinfunction "A2_A2") (pintype "bidirectional"))
    )
    (net (code "72") (name "unconnected-(U$2-PadA3)") (class "Default")
      (node (ref "U$2") (pin "A3") (pinfunction "A3_A3") (pintype "bidirectional"))
    )
    (net (code "73") (name "unconnected-(U$2-PadA4)") (class "Default")
      (node (ref "U$2") (pin "A4") (pinfunction "A4_A4") (pintype "bidirectional"))
    )
    (net (code "74") (name "unconnected-(U$2-PadA5)") (class "Default")
      (node (ref "U$2") (pin "A5") (pinfunction "A5_A5") (pintype "bidirectional"))
    )
    (net (code "75") (name "unconnected-(U$2-PadA6)") (class "Default")
      (node (ref "U$2") (pin "A6") (pinfunction "A6_A6") (pintype "bidirectional"))
    )
    (net (code "76") (name "unconnected-(U$2-PadA7)") (class "Default")
      (node (ref "U$2") (pin "A7") (pinfunction "A7_A7") (pintype "bidirectional"))
    )
    (net (code "77") (name "unconnected-(U$2-PadD3)") (class "Default")
      (node (ref "U$2") (pin "D3") (pinfunction "D3_D3") (pintype "bidirectional"))
    )
    (net (code "78") (name "unconnected-(U$2-PadD4)") (class "Default")
      (node (ref "U$2") (pin "D4") (pinfunction "D4_D4") (pintype "bidirectional"))
    )
    (net (code "79") (name "unconnected-(U$2-PadD5)") (class "Default")
      (node (ref "U$2") (pin "D5") (pinfunction "D5_D5") (pintype "bidirectional"))
    )
    (net (code "80") (name "unconnected-(U$2-PadD6)") (class "Default")
      (node (ref "U$2") (pin "D6") (pinfunction "D6_D6") (pintype "bidirectional"))
    )
    (net (code "81") (name "unconnected-(U$2-PadD7)") (class "Default")
      (node (ref "U$2") (pin "D7") (pinfunction "D7_D7") (pintype "bidirectional"))
    )
    (net (code "82") (name "unconnected-(U$2-PadDTR)") (class "Default")
      (node (ref "U$2") (pin "DTR") (pinfunction "DTR_DTR") (pintype "bidirectional"))
    )
    (net (code "83") (name "unconnected-(U$2-PadRAW)") (class "Default")
      (node (ref "U$2") (pin "RAW") (pinfunction "RAW_RAW") (pintype "bidirectional"))
    )
    (net (code "84") (name "unconnected-(U$2-PadRST)") (class "Default")
      (node (ref "U$2") (pin "RST") (pinfunction "RST_RST") (pintype "bidirectional"))
    )
    (net (code "85") (name "unconnected-(U$2-PadRST1)") (class "Default")
      (node (ref "U$2") (pin "RST1") (pinfunction "RST1_RST1") (pintype "bidirectional"))
    )
    (net (code "86") (name "unconnected-(U$2-PadRX1-1)") (class "Default")
      (node (ref "U$2") (pin "RX1-1") (pinfunction "RX1-1_RX1-1") (pintype "bidirectional"))
    )
    (net (code "87") (name "unconnected-(U$2-PadTX0-1)") (class "Default")
      (node (ref "U$2") (pin "TX0-1") (pinfunction "TX0-1_TX0-1") (pintype "bidirectional"))
    )
    (net (code "88") (name "unconnected-(U$2-PadVCC1)") (class "Default")
      (node (ref "U$2") (pin "VCC1") (pinfunction "VCC1_VCC1") (pintype "bidirectional"))
    )
    (net (code "89") (name "unconnected-(U$3-PadGPIO2)") (class "Default")
      (node (ref "U$3") (pin "GPIO2") (pinfunction "GPIO2_GPIO2") (pintype "bidirectional"))
    )
    (net (code "90") (name "unconnected-(U$3-PadRST)") (class "Default")
      (node (ref "U$3") (pin "RST") (pinfunction "RST_RST") (pintype "bidirectional"))
    )
  )
)
